# Heating.net
KiCad netlist of a schematic drawn in Altium Designer
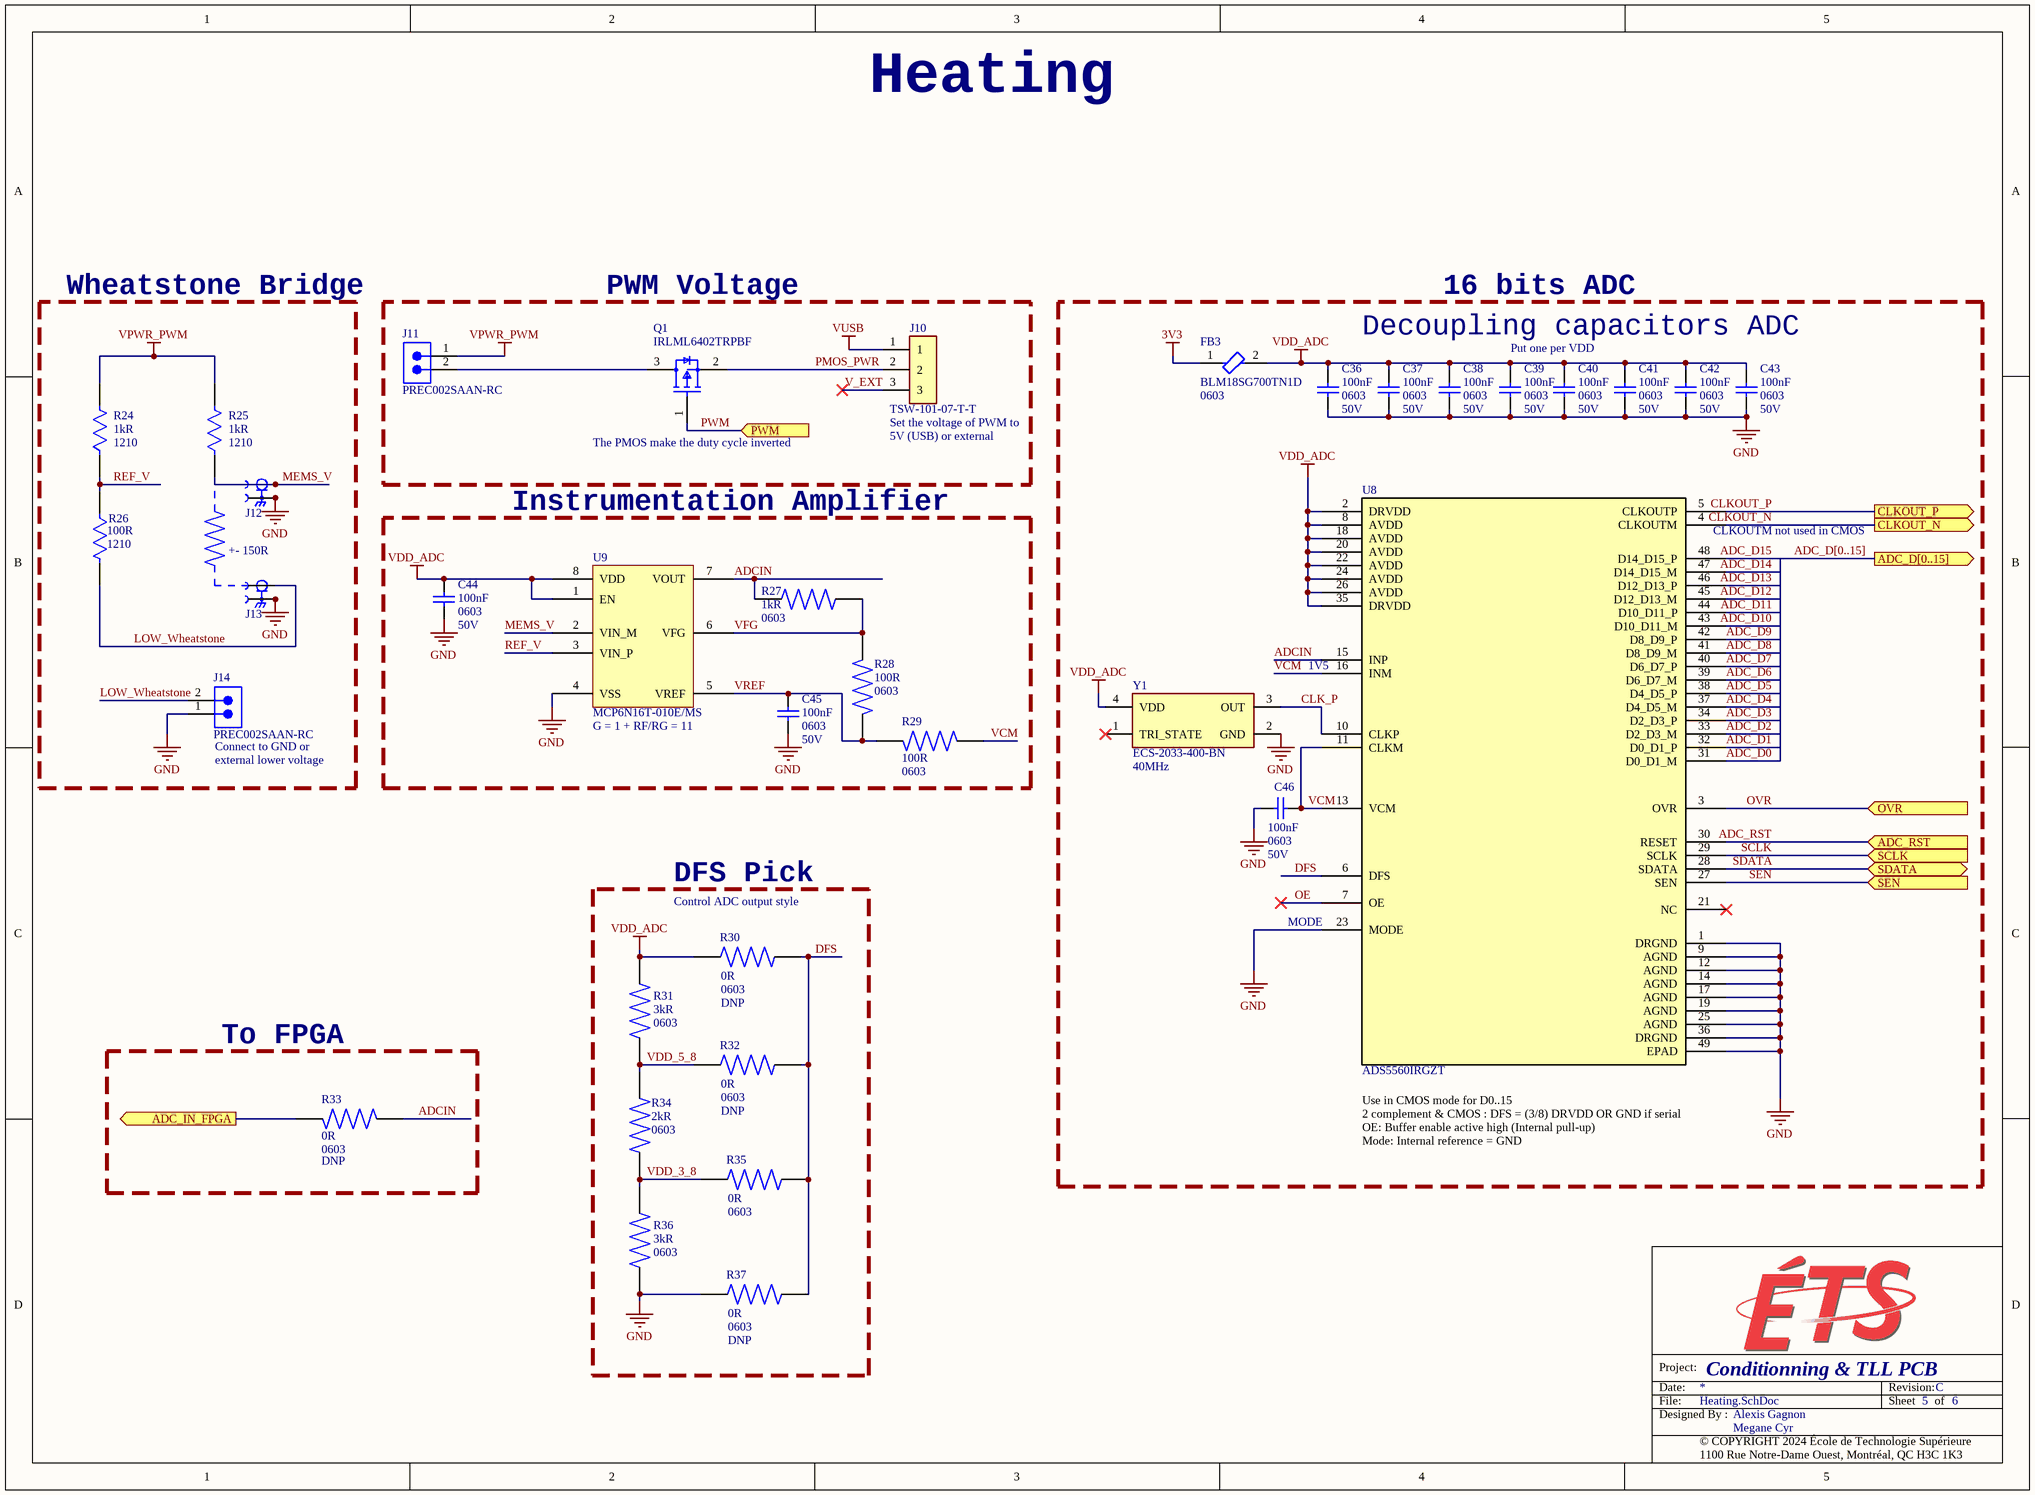
[diagram p0: Heating.SchDoc]

(export (version "E")
  (design (tool "Eeschema 10.0.6"))
  (components
    (comp (ref "C36")
      (value "100nF")
      (footprint "ANTC1608X90N")
      (description "CAP CER 0.1UF 50V X7R 0603")
      (fields
        (field (name "MANUFACTURER") "Samsung")
        (field (name "MANUFACTURER PART NUMBER") "CL10B104KB8NNWC")
        (field (name "CASE/PACKAGE") "0603")
        (field (name "VOLTAGE RATING") "50V")
      )
      (libsource (lib "ETS_Library") (part "CL10B104KB8NNWC"))
    )
    (comp (ref "C37")
      (value "100nF")
      (footprint "ANTC1608X90N")
      (description "CAP CER 0.1UF 50V X7R 0603")
      (fields
        (field (name "MANUFACTURER") "Samsung")
        (field (name "MANUFACTURER PART NUMBER") "CL10B104KB8NNWC")
        (field (name "CASE/PACKAGE") "0603")
        (field (name "VOLTAGE RATING") "50V")
      )
      (libsource (lib "ETS_Library") (part "CL10B104KB8NNWC"))
    )
    (comp (ref "C38")
      (value "100nF")
      (footprint "ANTC1608X90N")
      (description "CAP CER 0.1UF 50V X7R 0603")
      (fields
        (field (name "MANUFACTURER") "Samsung")
        (field (name "MANUFACTURER PART NUMBER") "CL10B104KB8NNWC")
        (field (name "CASE/PACKAGE") "0603")
        (field (name "VOLTAGE RATING") "50V")
      )
      (libsource (lib "ETS_Library") (part "CL10B104KB8NNWC"))
    )
    (comp (ref "C39")
      (value "100nF")
      (footprint "ANTC1608X90N")
      (description "CAP CER 0.1UF 50V X7R 0603")
      (fields
        (field (name "MANUFACTURER") "Samsung")
        (field (name "MANUFACTURER PART NUMBER") "CL10B104KB8NNWC")
        (field (name "CASE/PACKAGE") "0603")
        (field (name "VOLTAGE RATING") "50V")
      )
      (libsource (lib "ETS_Library") (part "CL10B104KB8NNWC"))
    )
    (comp (ref "C40")
      (value "100nF")
      (footprint "ANTC1608X90N")
      (description "CAP CER 0.1UF 50V X7R 0603")
      (fields
        (field (name "MANUFACTURER") "Samsung")
        (field (name "MANUFACTURER PART NUMBER") "CL10B104KB8NNWC")
        (field (name "CASE/PACKAGE") "0603")
        (field (name "VOLTAGE RATING") "50V")
      )
      (libsource (lib "ETS_Library") (part "CL10B104KB8NNWC"))
    )
    (comp (ref "C41")
      (value "100nF")
      (footprint "ANTC1608X90N")
      (description "CAP CER 0.1UF 50V X7R 0603")
      (fields
        (field (name "MANUFACTURER") "Samsung")
        (field (name "MANUFACTURER PART NUMBER") "CL10B104KB8NNWC")
        (field (name "CASE/PACKAGE") "0603")
        (field (name "VOLTAGE RATING") "50V")
      )
      (libsource (lib "ETS_Library") (part "CL10B104KB8NNWC"))
    )
    (comp (ref "C42")
      (value "100nF")
      (footprint "ANTC1608X90N")
      (description "CAP CER 0.1UF 50V X7R 0603")
      (fields
        (field (name "MANUFACTURER") "Samsung")
        (field (name "MANUFACTURER PART NUMBER") "CL10B104KB8NNWC")
        (field (name "CASE/PACKAGE") "0603")
        (field (name "VOLTAGE RATING") "50V")
      )
      (libsource (lib "ETS_Library") (part "CL10B104KB8NNWC"))
    )
    (comp (ref "C43")
      (value "100nF")
      (footprint "ANTC1608X90N")
      (description "CAP CER 0.1UF 50V X7R 0603")
      (fields
        (field (name "MANUFACTURER") "Samsung")
        (field (name "MANUFACTURER PART NUMBER") "CL10B104KB8NNWC")
        (field (name "CASE/PACKAGE") "0603")
        (field (name "VOLTAGE RATING") "50V")
      )
      (libsource (lib "ETS_Library") (part "CL10B104KB8NNWC"))
    )
    (comp (ref "C44")
      (value "100nF")
      (footprint "ANTC1608X90N")
      (description "CAP CER 0.1UF 50V X7R 0603")
      (fields
        (field (name "MANUFACTURER") "Samsung")
        (field (name "MANUFACTURER PART NUMBER") "CL10B104KB8NNWC")
        (field (name "CASE/PACKAGE") "0603")
        (field (name "VOLTAGE RATING") "50V")
      )
      (libsource (lib "ETS_Library") (part "CL10B104KB8NNWC"))
    )
    (comp (ref "C45")
      (value "100nF")
      (footprint "ANTC1608X90N")
      (description "CAP CER 0.1UF 50V X7R 0603")
      (fields
        (field (name "MANUFACTURER") "Samsung")
        (field (name "MANUFACTURER PART NUMBER") "CL10B104KB8NNWC")
        (field (name "CASE/PACKAGE") "0603")
        (field (name "VOLTAGE RATING") "50V")
      )
      (libsource (lib "ETS_Library") (part "CL10B104KB8NNWC"))
    )
    (comp (ref "C46")
      (value "100nF")
      (footprint "ANTC1608X90N")
      (description "CAP CER 0.1UF 50V X7R 0603")
      (fields
        (field (name "MANUFACTURER") "Samsung")
        (field (name "MANUFACTURER PART NUMBER") "CL10B104KB8NNWC")
        (field (name "CASE/PACKAGE") "0603")
        (field (name "VOLTAGE RATING") "50V")
      )
      (libsource (lib "ETS_Library") (part "CL10B104KB8NNWC"))
    )
    (comp (ref "FB3")
      (value "BLM18SG700TN1D")
      (footprint "BMS:BLM18SG700TN1D-MFG")
      (description "FERRITE BEAD 70 OHM 0603 1LN")
      (fields
        (field (name "TOLERANCE") "25%")
        (field (name "MANUFACTURER") "Murata")
        (field (name "CASE CODE (IMPERIAL)") "0603")
      )
      (libsource (lib "BMS") (part "BLM18SG700TN1D"))
    )
    (comp (ref "J10")
      (value "TSW-101-07-T-T")
      (footprint "SAMTEC_TSW-101-07-T-T")
      (fields (field (name "MF") "Samtec"))
      (libsource (lib "ETS_Library") (part "TSW-101-07-T-T"))
    )
    (comp (ref "J11")
      (value "PREC002SAAN-RC")
      (footprint "CONN_PREC002SAAN-RC_SUL")
      (description "CONN HEADER .100 SNGL STR 2POS")
      (fields (field (name "MANUFACTURER") "Sullins"))
      (libsource (lib "ETS_Library") (part "PREC002SAAN-RC"))
    )
    (comp (ref "J12")
      (value "CONSMA001-G")
      (footprint "LINX_CONSMA001-G")
      (description "CONN SMA RCPT STR 50 OHM PCB")
      (libsource (lib "ETS_Library") (part "CONSMA001-G"))
    )
    (comp (ref "J13")
      (value "CONSMA001-G")
      (footprint "LINX_CONSMA001-G")
      (description "CONN SMA RCPT STR 50 OHM PCB")
      (libsource (lib "ETS_Library") (part "CONSMA001-G"))
    )
    (comp (ref "J14")
      (value "PREC002SAAN-RC")
      (footprint "CONN_PREC002SAAN-RC_SUL")
      (description "CONN HEADER .100 SNGL STR 2POS")
      (fields (field (name "MANUFACTURER") "Sullins"))
      (libsource (lib "ETS_Library") (part "PREC002SAAN-RC"))
    )
    (comp (ref "Q1")
      (value "IRLML6402TRPBF")
      (footprint "FP-Micro3-MFG")
      (description "MOSFET P-CH 20V 3.7A SOT-23")
      (fields
        (field (name "OCTOPART") "https://octopart.com/irlml6402trpbf-infineon-65874989")
        (field (name "MANUFACTURER") "Infineon")
      )
      (libsource (lib "ETS_Library") (part "IRLML6402TRPBF"))
    )
    (comp (ref "R24")
      (value "ESR25JZPJ102")
      (footprint "FP-ESR25-MFG")
      (description "RES 1K OHM 5% 1W 1210")
      (fields
        (field (name "TOLERANCE") "5%")
        (field (name "CASE CODE (IMPERIAL)") "1210")
        (field (name "RESISTANCE") "1kR")
      )
      (libsource (lib "ETS_Library") (part "CMP-08839-027853-1"))
    )
    (comp (ref "R25")
      (value "ESR25JZPJ102")
      (footprint "FP-ESR25-MFG")
      (description "RES 1K OHM 5% 1W 1210")
      (fields
        (field (name "TOLERANCE") "5%")
        (field (name "CASE CODE (IMPERIAL)") "1210")
        (field (name "RESISTANCE") "1kR")
      )
      (libsource (lib "ETS_Library") (part "CMP-08839-027853-1"))
    )
    (comp (ref "R26")
      (value "ESR25JZPJ101")
      (footprint "FP-ESR25-MFG")
      (description "RES 100 OHM 5% 1W 1210")
      (fields
        (field (name "TOLERANCE") "5%")
        (field (name "CASE/PACKAGE") "1210")
        (field (name "RESISTANCE") "100R")
      )
      (libsource (lib "ETS_Library") (part "CMP-08839-028974-1"))
    )
    (comp (ref "R27")
      (value "1kR")
      (footprint "RC0603N_YAG")
      (fields
        (field (name "MANUFACTURER") "Yageo")
        (field (name "MANUFACTURER PART NUMBER") "RC0603FR-071KL")
        (field (name "TOLERANCE") "1%")
        (field (name "CASE/PACKAGE") "0603")
      )
      (libsource (lib "ETS_Library") (part "RC0603FR-071KL"))
    )
    (comp (ref "R28")
      (value "100R")
      (footprint "RC0603N_YAG")
      (fields
        (field (name "MANUFACTURER") "Yageo")
        (field (name "MANUFACTURER PART NUMBER") "RC0603FR-07100RL")
        (field (name "TOLERANCE") "1%")
        (field (name "CASE/PACKAGE") "0603")
      )
      (libsource (lib "ETS_Library") (part "RC0605FR-07100RL"))
    )
    (comp (ref "R29")
      (value "100R")
      (footprint "RC0603N_YAG")
      (fields
        (field (name "MANUFACTURER") "Yageo")
        (field (name "MANUFACTURER PART NUMBER") "RC0603FR-07100RL")
        (field (name "TOLERANCE") "1%")
        (field (name "CASE/PACKAGE") "0603")
      )
      (libsource (lib "ETS_Library") (part "RC0605FR-07100RL"))
    )
    (comp (ref "R30")
      (value "0R")
      (footprint "RES_RC0603_YAG")
      (description "Metal Glaze/thick Film, 0.1W, 0ohm, Surface Mount, 0603")
      (fields
        (field (name "MANUFACTURER") "Yageo")
        (field (name "MANUFACTURER PART NUMBER") "RC0603JR-070RL")
        (field (name "CASE/PACKAGE") "0603")
      )
      (libsource (lib "ETS_Library") (part "RC0603JR-070RL"))
    )
    (comp (ref "R31")
      (value "3kR")
      (footprint "RC0603N_YAG")
      (description "RES SMD 3K OHM 1% 1/10W 0603")
      (fields
        (field (name "MANUFACTURER") "Vishay")
        (field (name "MANUFACTURER PART NUMBER") "CRCW06033K00FKEA")
        (field (name "CASE/PACKAGE") "0603")
      )
      (libsource (lib "ETS_Library") (part "CRCW06033K00FKEA"))
    )
    (comp (ref "R32")
      (value "0R")
      (footprint "RES_RC0603_YAG")
      (description "Metal Glaze/thick Film, 0.1W, 0ohm, Surface Mount, 0603")
      (fields
        (field (name "MANUFACTURER") "Yageo")
        (field (name "MANUFACTURER PART NUMBER") "RC0603JR-070RL")
        (field (name "CASE/PACKAGE") "0603")
      )
      (libsource (lib "ETS_Library") (part "RC0603JR-070RL"))
    )
    (comp (ref "R33")
      (value "0R")
      (footprint "RESC1508X55N")
      (description "0 Ohms Jumper 0.1W, 1/10W Chip Resistor 0603 (1608 Metric) Automotive AEC-Q200 Thick Film")
      (fields
        (field (name "PACKAGE") "0603")
        (field (name "MF") "Stackpole Electronics")
        (field (name "MP") "RMCF0603ZT0R00")
      )
      (libsource (lib "ETS_Library") (part "RMCF0603ZT0R00"))
    )
    (comp (ref "R34")
      (value "2kR")
      (footprint "RC0603N_YAG")
      (description "RES SMD 2K OHM 1% 1/3W 0603")
      (fields
        (field (name "MANUFACTURER") "Vishay")
        (field (name "MANUFACTURER PART NUMBER") "CRCW06032K00FKEA")
        (field (name "CASE/PACKAGE") "0603")
      )
      (libsource (lib "ETS_Library") (part "CRCW06032K00FKEAHP"))
    )
    (comp (ref "R35")
      (value "0R")
      (footprint "RES_RC0603_YAG")
      (description "Metal Glaze/thick Film, 0.1W, 0ohm, Surface Mount, 0603")
      (fields
        (field (name "MANUFACTURER") "Yageo")
        (field (name "MANUFACTURER PART NUMBER") "RC0603JR-070RL")
        (field (name "CASE/PACKAGE") "0603")
      )
      (libsource (lib "ETS_Library") (part "RC0603JR-070RL"))
    )
    (comp (ref "R36")
      (value "3kR")
      (footprint "RC0603N_YAG")
      (description "RES SMD 3K OHM 1% 1/10W 0603")
      (fields
        (field (name "MANUFACTURER") "Vishay")
        (field (name "MANUFACTURER PART NUMBER") "CRCW06033K00FKEA")
        (field (name "CASE/PACKAGE") "0603")
      )
      (libsource (lib "ETS_Library") (part "CRCW06033K00FKEA"))
    )
    (comp (ref "R37")
      (value "0R")
      (footprint "RES_RC0603_YAG")
      (description "Metal Glaze/thick Film, 0.1W, 0ohm, Surface Mount, 0603")
      (fields
        (field (name "MANUFACTURER") "Yageo")
        (field (name "MANUFACTURER PART NUMBER") "RC0603JR-070RL")
        (field (name "CASE/PACKAGE") "0603")
      )
      (libsource (lib "ETS_Library") (part "RC0603JR-070RL"))
    )
    (comp (ref "U8")
      (value "ADS5560IRGZT")
      (footprint "RGZ48_5P15X5P15")
      (description "16-Bit, 40-MSPS Analog-to-Digital Converter (ADC) 48-VQFN -40 to 85")
      (fields (field (name "COPYRIGHT") "Copyright (C) 2025 Ultra Librarian. All rights reserved."))
      (libsource (lib "ETS_Library") (part "ADS5560IRGZT"))
    )
    (comp (ref "U9")
      (value "MCP6N16T-010E/MS")
      (footprint "SOP65P490X110-8N")
      (description "IC INST AMP 1 CIRCUIT 8MSOP")
      (fields (field (name "MANUFACTURER") "Microchip"))
      (libsource (lib "ETS_Library") (part "MCP6N16T-010E/MS"))
    )
    (comp (ref "Y1")
      (value "ECS-2033-400-BN")
      (footprint "OSC_ECS-2033-400-BN")
      (description "subminiature SMD oscillators")
      (fields (field (name "ALTIUM_VALUE") "40MHz"))
      (libsource (lib "ETS_Library") (part "ECS-2033-400-BN"))
    )
  )
  (nets
    (net (code "1") (name "/ADCIN") (class "Default")
      (node (ref "R27") (pin "2") (pinfunction "2_2") (pintype "passive"))
      (node (ref "R33") (pin "1") (pinfunction "1_1") (pintype "passive"))
      (node (ref "U8") (pin "15") (pinfunction "INP_15") (pintype "passive"))
      (node (ref "U9") (pin "7") (pinfunction "VOUT_7") (pintype "passive"))
    )
    (net (code "2") (name "/ADC_D0") (class "Default")
      (node (ref "U8") (pin "31") (pinfunction "D0_D1_M_31") (pintype "passive"))
    )
    (net (code "3") (name "/ADC_D1") (class "Default")
      (node (ref "U8") (pin "32") (pinfunction "D0_D1_P_32") (pintype "passive"))
    )
    (net (code "4") (name "/ADC_D2") (class "Default")
      (node (ref "U8") (pin "33") (pinfunction "D2_D3_M_33") (pintype "passive"))
    )
    (net (code "5") (name "/ADC_D3") (class "Default")
      (node (ref "U8") (pin "34") (pinfunction "D2_D3_P_34") (pintype "passive"))
    )
    (net (code "6") (name "/ADC_D4") (class "Default")
      (node (ref "U8") (pin "37") (pinfunction "D4_D5_M_37") (pintype "passive"))
    )
    (net (code "7") (name "/ADC_D5") (class "Default")
      (node (ref "U8") (pin "38") (pinfunction "D4_D5_P_38") (pintype "passive"))
    )
    (net (code "8") (name "/ADC_D6") (class "Default")
      (node (ref "U8") (pin "39") (pinfunction "D6_D7_M_39") (pintype "passive"))
    )
    (net (code "9") (name "/ADC_D7") (class "Default")
      (node (ref "U8") (pin "40") (pinfunction "D6_D7_P_40") (pintype "passive"))
    )
    (net (code "10") (name "/ADC_D8") (class "Default")
      (node (ref "U8") (pin "41") (pinfunction "D8_D9_M_41") (pintype "passive"))
    )
    (net (code "11") (name "/ADC_D9") (class "Default")
      (node (ref "U8") (pin "42") (pinfunction "D8_D9_P_42") (pintype "passive"))
    )
    (net (code "12") (name "/ADC_D10") (class "Default")
      (node (ref "U8") (pin "43") (pinfunction "D10_D11_M_43") (pintype "passive"))
    )
    (net (code "13") (name "/ADC_D11") (class "Default")
      (node (ref "U8") (pin "44") (pinfunction "D10_D11_P_44") (pintype "passive"))
    )
    (net (code "14") (name "/ADC_D12") (class "Default")
      (node (ref "U8") (pin "45") (pinfunction "D12_D13_M_45") (pintype "passive"))
    )
    (net (code "15") (name "/ADC_D13") (class "Default")
      (node (ref "U8") (pin "46") (pinfunction "D12_D13_P_46") (pintype "passive"))
    )
    (net (code "16") (name "/ADC_D14") (class "Default")
      (node (ref "U8") (pin "47") (pinfunction "D14_D15_M_47") (pintype "passive"))
    )
    (net (code "17") (name "/ADC_D15") (class "Default")
      (node (ref "U8") (pin "48") (pinfunction "D14_D15_P_48") (pintype "passive"))
    )
    (net (code "19") (name "/ADC_IN_FPGA") (class "Default")
      (node (ref "R33") (pin "2") (pinfunction "2_2") (pintype "passive"))
    )
    (net (code "20") (name "/ADC_RST") (class "Default")
      (node (ref "U8") (pin "30") (pinfunction "RESET_30") (pintype "passive"))
    )
    (net (code "21") (name "/CLKOUT_N") (class "Default")
      (node (ref "U8") (pin "4") (pinfunction "CLKOUTM_4") (pintype "passive"))
    )
    (net (code "22") (name "/CLKOUT_P") (class "Default")
      (node (ref "U8") (pin "5") (pinfunction "CLKOUTP_5") (pintype "passive"))
    )
    (net (code "23") (name "/CLK_P") (class "Default")
      (node (ref "U8") (pin "10") (pinfunction "CLKP_10") (pintype "passive"))
      (node (ref "Y1") (pin "3") (pinfunction "OUT_3") (pintype "passive"))
    )
    (net (code "24") (name "/DFS") (class "Default")
      (node (ref "R30") (pin "2") (pinfunction "2_2") (pintype "passive"))
      (node (ref "R32") (pin "2") (pinfunction "2_2") (pintype "passive"))
      (node (ref "R35") (pin "2") (pinfunction "2_2") (pintype "passive"))
      (node (ref "R37") (pin "2") (pinfunction "2_2") (pintype "passive"))
      (node (ref "U8") (pin "6") (pinfunction "DFS_6") (pintype "passive"))
    )
    (net (code "25") (name "/LOW_Wheatstone") (class "Default")
      (node (ref "J13") (pin "1") (pinfunction "1_1") (pintype "passive"))
      (node (ref "J14") (pin "2") (pinfunction "2_2") (pintype "passive"))
      (node (ref "R26") (pin "2") (pinfunction "2_2") (pintype "passive"))
    )
    (net (code "26") (name "/MEMS_V") (class "Default")
      (node (ref "J12") (pin "1") (pinfunction "1_1") (pintype "passive"))
      (node (ref "R25") (pin "1") (pinfunction "1_1") (pintype "passive"))
      (node (ref "U9") (pin "2") (pinfunction "VIN_M_2") (pintype "passive"))
    )
    (net (code "27") (name "/OE") (class "Default")
      (node (ref "U8") (pin "7") (pinfunction "OE_7") (pintype "passive+no_connect"))
    )
    (net (code "28") (name "/OVR") (class "Default")
      (node (ref "U8") (pin "3") (pinfunction "OVR_3") (pintype "passive"))
    )
    (net (code "29") (name "/PMOS_PWR") (class "Default")
      (node (ref "J10") (pin "2") (pinfunction "2_2") (pintype "passive"))
      (node (ref "Q1") (pin "2") (pinfunction "S_2") (pintype "passive"))
    )
    (net (code "30") (name "/PWM") (class "Default")
      (node (ref "Q1") (pin "1") (pinfunction "G_1") (pintype "passive"))
    )
    (net (code "31") (name "/REF_V") (class "Default")
      (node (ref "R24") (pin "1") (pinfunction "1_1") (pintype "passive"))
      (node (ref "R26") (pin "1") (pinfunction "1_1") (pintype "passive"))
      (node (ref "U9") (pin "3") (pinfunction "VIN_P_3") (pintype "passive"))
    )
    (net (code "32") (name "/SCLK") (class "Default")
      (node (ref "U8") (pin "29") (pinfunction "SCLK_29") (pintype "passive"))
    )
    (net (code "33") (name "/SDATA") (class "Default")
      (node (ref "U8") (pin "28") (pinfunction "SDATA_28") (pintype "passive"))
    )
    (net (code "34") (name "/SEN") (class "Default")
      (node (ref "U8") (pin "27") (pinfunction "SEN_27") (pintype "passive"))
    )
    (net (code "35") (name "/VCM") (class "Default")
      (node (ref "C46") (pin "1") (pinfunction "1_1") (pintype "passive"))
      (node (ref "R29") (pin "2") (pinfunction "2_2") (pintype "passive"))
      (node (ref "U8") (pin "11") (pinfunction "CLKM_11") (pintype "passive"))
      (node (ref "U8") (pin "13") (pinfunction "VCM_13") (pintype "passive"))
      (node (ref "U8") (pin "16") (pinfunction "INM_16") (pintype "passive"))
    )
    (net (code "36") (name "/VDD_3_8") (class "Default")
      (node (ref "R34") (pin "1") (pinfunction "1_1") (pintype "passive"))
      (node (ref "R35") (pin "1") (pinfunction "1_1") (pintype "passive"))
      (node (ref "R36") (pin "2") (pinfunction "2_2") (pintype "passive"))
    )
    (net (code "37") (name "/VDD_5_8") (class "Default")
      (node (ref "R31") (pin "1") (pinfunction "1_1") (pintype "passive"))
      (node (ref "R32") (pin "1") (pinfunction "1_1") (pintype "passive"))
      (node (ref "R34") (pin "2") (pinfunction "2_2") (pintype "passive"))
    )
    (net (code "38") (name "/VFG") (class "Default")
      (node (ref "R27") (pin "1") (pinfunction "1_1") (pintype "passive"))
      (node (ref "R28") (pin "1") (pinfunction "1_1") (pintype "passive"))
      (node (ref "U9") (pin "6") (pinfunction "VFG_6") (pintype "passive"))
    )
    (net (code "39") (name "/VREF") (class "Default")
      (node (ref "C45") (pin "1") (pinfunction "1_1") (pintype "passive"))
      (node (ref "R28") (pin "2") (pinfunction "2_2") (pintype "passive"))
      (node (ref "R29") (pin "1") (pinfunction "1_1") (pintype "passive"))
      (node (ref "U9") (pin "5") (pinfunction "VREF_5") (pintype "passive"))
    )
    (net (code "40") (name "/V_EXT") (class "Default")
      (node (ref "J10") (pin "3") (pinfunction "3_3") (pintype "passive+no_connect"))
    )
    (net (code "41") (name "3V3") (class "Default")
      (node (ref "FB3") (pin "1") (pinfunction "1_1") (pintype "passive"))
    )
    (net (code "42") (name "GND") (class "Default")
      (node (ref "C36") (pin "2") (pinfunction "2_2") (pintype "passive"))
      (node (ref "C37") (pin "2") (pinfunction "2_2") (pintype "passive"))
      (node (ref "C38") (pin "2") (pinfunction "2_2") (pintype "passive"))
      (node (ref "C39") (pin "2") (pinfunction "2_2") (pintype "passive"))
      (node (ref "C40") (pin "2") (pinfunction "2_2") (pintype "passive"))
      (node (ref "C41") (pin "2") (pinfunction "2_2") (pintype "passive"))
      (node (ref "C42") (pin "2") (pinfunction "2_2") (pintype "passive"))
      (node (ref "C43") (pin "2") (pinfunction "2_2") (pintype "passive"))
      (node (ref "C44") (pin "2") (pinfunction "2_2") (pintype "passive"))
      (node (ref "C45") (pin "2") (pinfunction "2_2") (pintype "passive"))
      (node (ref "C46") (pin "2") (pinfunction "2_2") (pintype "passive"))
      (node (ref "J12") (pin "S1") (pinfunction "2_S1") (pintype "passive"))
      (node (ref "J12") (pin "S2") (pinfunction "2_S2") (pintype "passive"))
      (node (ref "J12") (pin "S3") (pinfunction "2_S3") (pintype "passive"))
      (node (ref "J12") (pin "S4") (pinfunction "2_S4") (pintype "passive"))
      (node (ref "J13") (pin "S1") (pinfunction "2_S1") (pintype "passive"))
      (node (ref "J13") (pin "S2") (pinfunction "2_S2") (pintype "passive"))
      (node (ref "J13") (pin "S3") (pinfunction "2_S3") (pintype "passive"))
      (node (ref "J13") (pin "S4") (pinfunction "2_S4") (pintype "passive"))
      (node (ref "J14") (pin "1") (pinfunction "1_1") (pintype "passive"))
      (node (ref "R36") (pin "1") (pinfunction "1_1") (pintype "passive"))
      (node (ref "R37") (pin "1") (pinfunction "1_1") (pintype "passive"))
      (node (ref "U8") (pin "1") (pinfunction "DRGND_1") (pintype "passive"))
      (node (ref "U8") (pin "12") (pinfunction "AGND_12") (pintype "passive"))
      (node (ref "U8") (pin "14") (pinfunction "AGND_14") (pintype "passive"))
      (node (ref "U8") (pin "17") (pinfunction "AGND_17") (pintype "passive"))
      (node (ref "U8") (pin "19") (pinfunction "AGND_19") (pintype "passive"))
      (node (ref "U8") (pin "23") (pinfunction "MODE_23") (pintype "passive"))
      (node (ref "U8") (pin "25") (pinfunction "AGND_25") (pintype "passive"))
      (node (ref "U8") (pin "36") (pinfunction "DRGND_36") (pintype "passive"))
      (node (ref "U8") (pin "49") (pinfunction "EPAD_49") (pintype "passive"))
      (node (ref "U8") (pin "9") (pinfunction "AGND_9") (pintype "passive"))
      (node (ref "U9") (pin "4") (pinfunction "VSS_4") (pintype "passive"))
      (node (ref "Y1") (pin "2") (pinfunction "GND_2") (pintype "power_in"))
    )
    (net (code "43") (name "Net-(Q1-D)") (class "Default")
      (node (ref "J11") (pin "2") (pinfunction "2_2") (pintype "passive"))
      (node (ref "Q1") (pin "3") (pinfunction "D_3") (pintype "passive"))
    )
    (net (code "44") (name "VDD_ADC") (class "Default")
      (node (ref "C36") (pin "1") (pinfunction "1_1") (pintype "passive"))
      (node (ref "C37") (pin "1") (pinfunction "1_1") (pintype "passive"))
      (node (ref "C38") (pin "1") (pinfunction "1_1") (pintype "passive"))
      (node (ref "C39") (pin "1") (pinfunction "1_1") (pintype "passive"))
      (node (ref "C40") (pin "1") (pinfunction "1_1") (pintype "passive"))
      (node (ref "C41") (pin "1") (pinfunction "1_1") (pintype "passive"))
      (node (ref "C42") (pin "1") (pinfunction "1_1") (pintype "passive"))
      (node (ref "C43") (pin "1") (pinfunction "1_1") (pintype "passive"))
      (node (ref "C44") (pin "1") (pinfunction "1_1") (pintype "passive"))
      (node (ref "FB3") (pin "2") (pinfunction "2_2") (pintype "passive"))
      (node (ref "R30") (pin "1") (pinfunction "1_1") (pintype "passive"))
      (node (ref "R31") (pin "2") (pinfunction "2_2") (pintype "passive"))
      (node (ref "U8") (pin "18") (pinfunction "AVDD_18") (pintype "passive"))
      (node (ref "U8") (pin "2") (pinfunction "DRVDD_2") (pintype "passive"))
      (node (ref "U8") (pin "20") (pinfunction "AVDD_20") (pintype "passive"))
      (node (ref "U8") (pin "22") (pinfunction "AVDD_22") (pintype "passive"))
      (node (ref "U8") (pin "24") (pinfunction "AVDD_24") (pintype "passive"))
      (node (ref "U8") (pin "26") (pinfunction "AVDD_26") (pintype "passive"))
      (node (ref "U8") (pin "35") (pinfunction "DRVDD_35") (pintype "passive"))
      (node (ref "U8") (pin "8") (pinfunction "AVDD_8") (pintype "passive"))
      (node (ref "U9") (pin "1") (pinfunction "EN_1") (pintype "passive"))
      (node (ref "U9") (pin "8") (pinfunction "VDD_8") (pintype "passive"))
      (node (ref "Y1") (pin "4") (pinfunction "VDD_4") (pintype "passive"))
    )
    (net (code "45") (name "VPWR_PWM") (class "Default")
      (node (ref "J11") (pin "1") (pinfunction "1_1") (pintype "passive"))
      (node (ref "R24") (pin "2") (pinfunction "2_2") (pintype "passive"))
      (node (ref "R25") (pin "2") (pinfunction "2_2") (pintype "passive"))
    )
    (net (code "46") (name "VUSB") (class "Default")
      (node (ref "J10") (pin "1") (pinfunction "1_1") (pintype "passive"))
    )
    (net (code "47") (name "unconnected-(U8-NC-Pad21)") (class "Default")
      (node (ref "U8") (pin "21") (pinfunction "NC_21") (pintype "passive+no_connect"))
    )
    (net (code "48") (name "unconnected-(Y1-TRI_STATE-Pad1)") (class "Default")
      (node (ref "Y1") (pin "1") (pinfunction "TRI_STATE_1") (pintype "passive+no_connect"))
    )
  )
)
